# mailbox.net
KiCad netlist of a schematic drawn in EAGLE
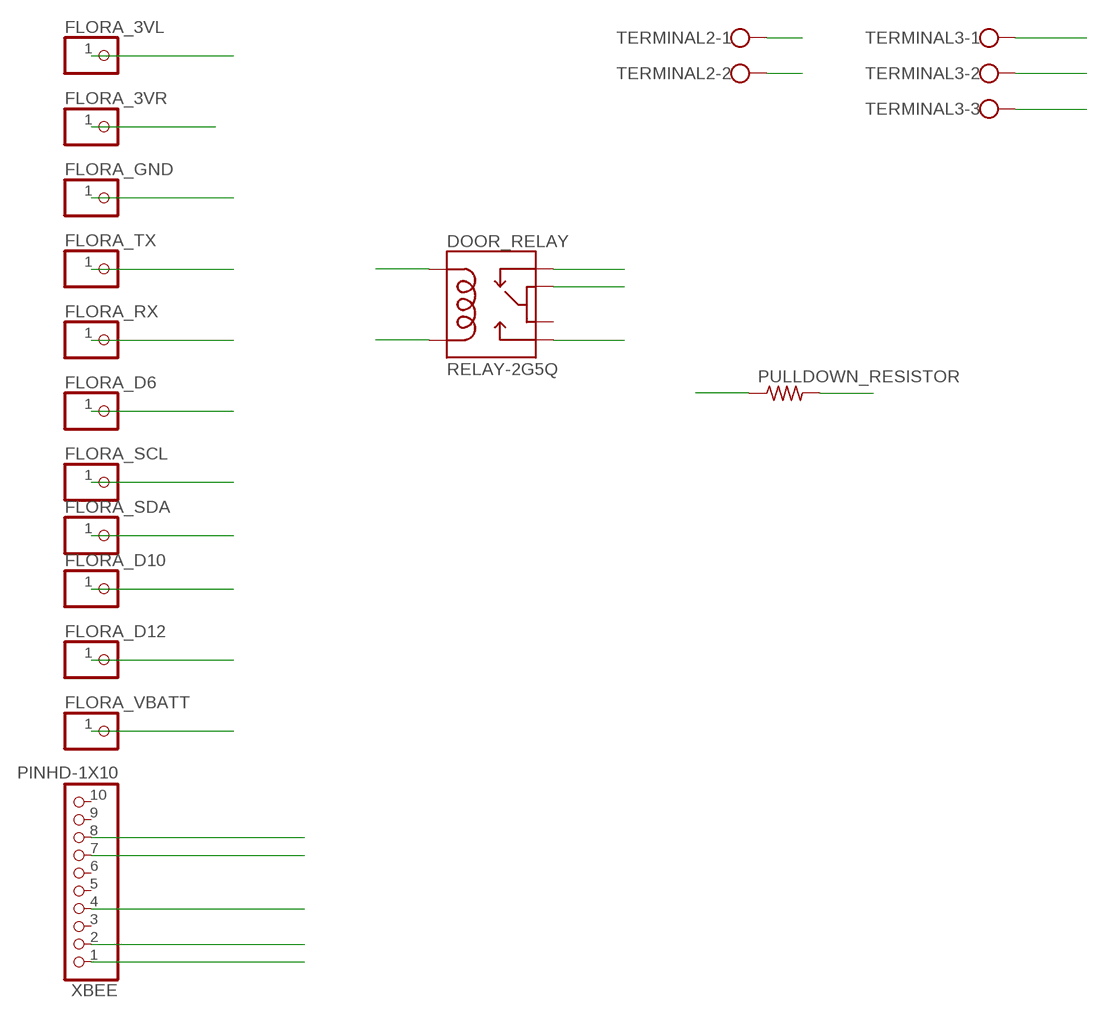
[diagram p0: schematic, sheet 1]

(export (version "E")
  (design (tool "Eeschema 10.0.6"))
  (components
    (comp (ref "DOOR_RELAY")
      (value "RELAY-2G5Q")
      (footprint "eagle-import:RELAY-G5V")
      (libsource (lib "eagle-import") (part "RELAY-2G5Q"))
    )
    (comp (ref "FLORA_3VL")
      (value "PINHD-1X1CB")
      (footprint "eagle-import:1X01-CLEANBIG")
      (libsource (lib "eagle-import") (part "PINHD-1X1CB"))
    )
    (comp (ref "FLORA_3VR")
      (value "PINHD-1X1CB")
      (footprint "eagle-import:1X01-CLEANBIG")
      (libsource (lib "eagle-import") (part "PINHD-1X1CB"))
    )
    (comp (ref "FLORA_D6")
      (value "PINHD-1X1CB")
      (footprint "eagle-import:1X01-CLEANBIG")
      (libsource (lib "eagle-import") (part "PINHD-1X1CB"))
    )
    (comp (ref "FLORA_D10")
      (value "PINHD-1X1CB")
      (footprint "eagle-import:1X01-CLEANBIG")
      (libsource (lib "eagle-import") (part "PINHD-1X1CB"))
    )
    (comp (ref "FLORA_D12")
      (value "PINHD-1X1CB")
      (footprint "eagle-import:1X01-CLEANBIG")
      (libsource (lib "eagle-import") (part "PINHD-1X1CB"))
    )
    (comp (ref "FLORA_GND")
      (value "PINHD-1X1CB")
      (footprint "eagle-import:1X01-CLEANBIG")
      (libsource (lib "eagle-import") (part "PINHD-1X1CB"))
    )
    (comp (ref "FLORA_RX")
      (value "PINHD-1X1CB")
      (footprint "eagle-import:1X01-CLEANBIG")
      (libsource (lib "eagle-import") (part "PINHD-1X1CB"))
    )
    (comp (ref "FLORA_SCL")
      (value "PINHD-1X1CB")
      (footprint "eagle-import:1X01-CLEANBIG")
      (libsource (lib "eagle-import") (part "PINHD-1X1CB"))
    )
    (comp (ref "FLORA_SDA")
      (value "PINHD-1X1CB")
      (footprint "eagle-import:1X01-CLEANBIG")
      (libsource (lib "eagle-import") (part "PINHD-1X1CB"))
    )
    (comp (ref "FLORA_TX")
      (value "PINHD-1X1CB")
      (footprint "eagle-import:1X01-CLEANBIG")
      (libsource (lib "eagle-import") (part "PINHD-1X1CB"))
    )
    (comp (ref "FLORA_VBATT")
      (value "PINHD-1X1CB")
      (footprint "eagle-import:1X01-CLEANBIG")
      (libsource (lib "eagle-import") (part "PINHD-1X1CB"))
    )
    (comp (ref "PULLDOWN_RESISTOR")
      (value "FLIPFLOP-RES")
      (footprint "eagle-import:0805-THM")
      (libsource (lib "eagle-import") (part "FLIPFLOP-RES"))
    )
    (comp (ref "TERMINAL2")
      (value "W237-102")
      (footprint "eagle-import:W237-102")
      (fields (field (name "MPN") "237-102"))
      (libsource (lib "eagle-import") (part "W237-102"))
    )
    (comp (ref "TERMINAL3")
      (value "W237-103")
      (footprint "eagle-import:W237-103")
      (fields (field (name "MPN") "237-103"))
      (libsource (lib "eagle-import") (part "W237-103"))
    )
    (comp (ref "XBEE")
      (value "PINHD-1X10")
      (footprint "eagle-import:1X10-BIG")
      (libsource (lib "eagle-import") (part "PINHD-1X10"))
    )
  )
  (nets
    (net (code "1") (name "/3VL") (class "Default")
      (node (ref "DOOR_RELAY") (pin "1") (pinfunction "1_1") (pintype "bidirectional"))
      (node (ref "DOOR_RELAY") (pin "2") (pinfunction "2_2") (pintype "bidirectional"))
      (node (ref "FLORA_3VL") (pin "1") (pinfunction "1_1") (pintype "passive"))
    )
    (net (code "2") (name "/3VR") (class "Default")
      (node (ref "FLORA_3VR") (pin "1") (pinfunction "1_1") (pintype "passive"))
      (node (ref "XBEE") (pin "1") (pinfunction "1_1") (pintype "passive"))
    )
    (net (code "3") (name "/D6") (class "Default")
      (node (ref "FLORA_D6") (pin "1") (pinfunction "1_1") (pintype "passive"))
      (node (ref "TERMINAL3") (pin "1") (pinfunction "KL_1") (pintype "passive"))
    )
    (net (code "4") (name "/D12") (class "Default")
      (node (ref "FLORA_D12") (pin "1") (pinfunction "1_1") (pintype "passive"))
      (node (ref "PULLDOWN_RESISTOR") (pin "1") (pinfunction "1_1") (pintype "passive"))
      (node (ref "TERMINAL3") (pin "2") (pinfunction "KL_2") (pintype "passive"))
    )
    (net (code "5") (name "/DOOR_SWITCH") (class "Default")
      (node (ref "DOOR_RELAY") (pin "9") (pinfunction "9_9") (pintype "bidirectional"))
      (node (ref "TERMINAL2") (pin "2") (pinfunction "KL_2") (pintype "passive"))
    )
    (net (code "6") (name "/GND") (class "Default")
      (node (ref "DOOR_RELAY") (pin "10") (pinfunction "10_10") (pintype "bidirectional"))
      (node (ref "FLORA_GND") (pin "1") (pinfunction "1_1") (pintype "passive"))
      (node (ref "PULLDOWN_RESISTOR") (pin "2") (pinfunction "2_2") (pintype "passive"))
      (node (ref "TERMINAL2") (pin "1") (pinfunction "KL_1") (pintype "passive"))
      (node (ref "XBEE") (pin "4") (pinfunction "4_4") (pintype "passive"))
    )
    (net (code "7") (name "/RX") (class "Default")
      (node (ref "FLORA_TX") (pin "1") (pinfunction "1_1") (pintype "passive"))
      (node (ref "XBEE") (pin "7") (pinfunction "7_7") (pintype "passive"))
    )
    (net (code "8") (name "/SCL") (class "Default")
      (node (ref "DOOR_RELAY") (pin "5") (pinfunction "5_5") (pintype "bidirectional"))
      (node (ref "FLORA_SCL") (pin "1") (pinfunction "1_1") (pintype "passive"))
    )
    (net (code "9") (name "/SDA") (class "Default")
      (node (ref "FLORA_SDA") (pin "1") (pinfunction "1_1") (pintype "passive"))
      (node (ref "XBEE") (pin "2") (pinfunction "2_2") (pintype "passive"))
    )
    (net (code "10") (name "/TX") (class "Default")
      (node (ref "FLORA_RX") (pin "1") (pinfunction "1_1") (pintype "passive"))
      (node (ref "XBEE") (pin "8") (pinfunction "8_8") (pintype "passive"))
    )
    (net (code "11") (name "/VBATT") (class "Default")
      (node (ref "FLORA_VBATT") (pin "1") (pinfunction "1_1") (pintype "passive"))
      (node (ref "TERMINAL3") (pin "3") (pinfunction "KL_3") (pintype "passive"))
    )
    (net (code "12") (name "unconnected-(DOOR_RELAY-Pad6)") (class "Default")
      (node (ref "DOOR_RELAY") (pin "6") (pinfunction "6_6") (pintype "bidirectional"))
    )
    (net (code "13") (name "unconnected-(FLORA_D10-Pad1)") (class "Default")
      (node (ref "FLORA_D10") (pin "1") (pinfunction "1_1") (pintype "passive"))
    )
    (net (code "14") (name "unconnected-(XBEE-Pad3)") (class "Default")
      (node (ref "XBEE") (pin "3") (pinfunction "3_3") (pintype "passive"))
    )
    (net (code "15") (name "unconnected-(XBEE-Pad5)") (class "Default")
      (node (ref "XBEE") (pin "5") (pinfunction "5_5") (pintype "passive"))
    )
    (net (code "16") (name "unconnected-(XBEE-Pad6)") (class "Default")
      (node (ref "XBEE") (pin "6") (pinfunction "6_6") (pintype "passive"))
    )
    (net (code "17") (name "unconnected-(XBEE-Pad9)") (class "Default")
      (node (ref "XBEE") (pin "9") (pinfunction "9_9") (pintype "passive"))
    )
    (net (code "18") (name "unconnected-(XBEE-Pad10)") (class "Default")
      (node (ref "XBEE") (pin "10") (pinfunction "10_10") (pintype "passive"))
    )
  )
)
